# LED_Driver_and_LEDs_01.net
KiCad netlist of a schematic drawn in Altium Designer
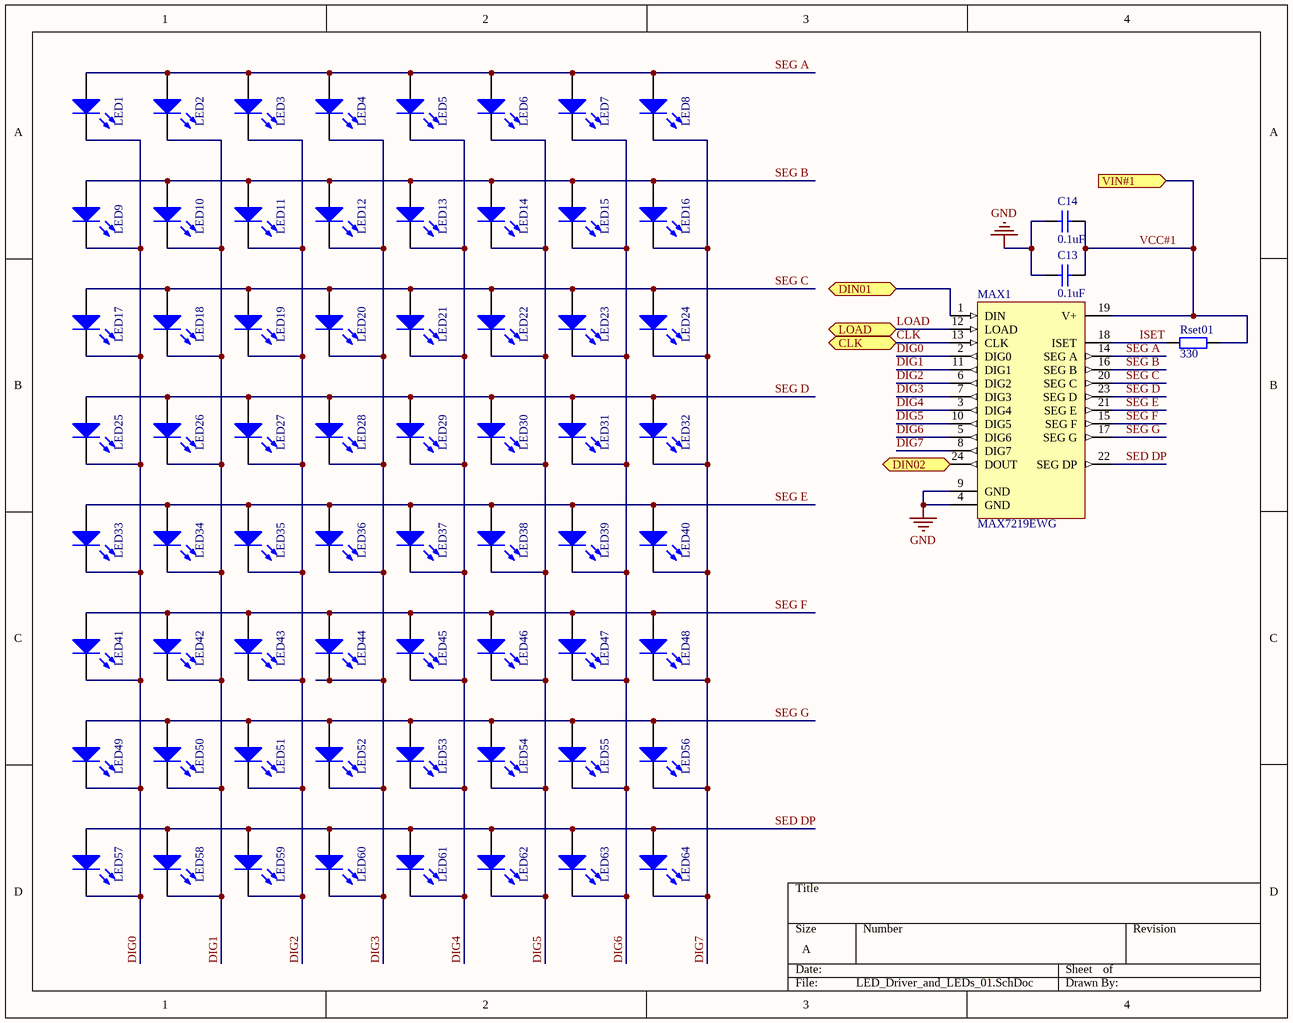
[diagram p0: LED_Driver_and_LEDs_01.SchDoc]

(export (version "E")
  (design (tool "Eeschema 10.0.6"))
  (components
    (comp (ref "C13")
      (value "0.1uF")
      (footprint "6-0805_N")
      (description "Capacitor (Semiconductor SIM Model)")
      (fields (field (name "Comment") "Cap Semi") (field (name "PUBLISHER") "Altium Limited"))
      (libsource (lib "Miscellaneous Devices") (part "Cap Semi"))
    )
    (comp (ref "C14")
      (value "0.1uF")
      (footprint "6-0805_N")
      (description "Capacitor (Semiconductor SIM Model)")
      (fields (field (name "Comment") "Cap Semi") (field (name "PUBLISHER") "Altium Limited"))
      (libsource (lib "Miscellaneous Devices") (part "Cap Semi"))
    )
    (comp (ref "LED1")
      (value "LED3")
      (footprint "3.5X2.8X1.9")
      (description "Typical BLUE SiC LED")
      (fields (field (name "PUBLISHER") "Altium Limited"))
      (libsource (lib "Miscellaneous Devices") (part "LED3"))
    )
    (comp (ref "LED2")
      (value "LED3")
      (footprint "3.5X2.8X1.9")
      (description "Typical BLUE SiC LED")
      (fields (field (name "PUBLISHER") "Altium Limited"))
      (libsource (lib "Miscellaneous Devices") (part "LED3"))
    )
    (comp (ref "LED3")
      (value "LED3")
      (footprint "3.5X2.8X1.9")
      (description "Typical BLUE SiC LED")
      (fields (field (name "PUBLISHER") "Altium Limited"))
      (libsource (lib "Miscellaneous Devices") (part "LED3"))
    )
    (comp (ref "LED4")
      (value "LED3")
      (footprint "3.5X2.8X1.9")
      (description "Typical BLUE SiC LED")
      (fields (field (name "PUBLISHER") "Altium Limited"))
      (libsource (lib "Miscellaneous Devices") (part "LED3"))
    )
    (comp (ref "LED5")
      (value "LED3")
      (footprint "3.5X2.8X1.9")
      (description "Typical BLUE SiC LED")
      (fields (field (name "PUBLISHER") "Altium Limited"))
      (libsource (lib "Miscellaneous Devices") (part "LED3"))
    )
    (comp (ref "LED6")
      (value "LED3")
      (footprint "3.5X2.8X1.9")
      (description "Typical BLUE SiC LED")
      (fields (field (name "PUBLISHER") "Altium Limited"))
      (libsource (lib "Miscellaneous Devices") (part "LED3"))
    )
    (comp (ref "LED7")
      (value "LED3")
      (footprint "3.5X2.8X1.9")
      (description "Typical BLUE SiC LED")
      (fields (field (name "PUBLISHER") "Altium Limited"))
      (libsource (lib "Miscellaneous Devices") (part "LED3"))
    )
    (comp (ref "LED8")
      (value "LED3")
      (footprint "3.5X2.8X1.9")
      (description "Typical BLUE SiC LED")
      (fields (field (name "PUBLISHER") "Altium Limited"))
      (libsource (lib "Miscellaneous Devices") (part "LED3"))
    )
    (comp (ref "LED9")
      (value "LED3")
      (footprint "3.5X2.8X1.9")
      (description "Typical BLUE SiC LED")
      (fields (field (name "PUBLISHER") "Altium Limited"))
      (libsource (lib "Miscellaneous Devices") (part "LED3"))
    )
    (comp (ref "LED10")
      (value "LED3")
      (footprint "3.5X2.8X1.9")
      (description "Typical BLUE SiC LED")
      (fields (field (name "PUBLISHER") "Altium Limited"))
      (libsource (lib "Miscellaneous Devices") (part "LED3"))
    )
    (comp (ref "LED11")
      (value "LED3")
      (footprint "3.5X2.8X1.9")
      (description "Typical BLUE SiC LED")
      (fields (field (name "PUBLISHER") "Altium Limited"))
      (libsource (lib "Miscellaneous Devices") (part "LED3"))
    )
    (comp (ref "LED12")
      (value "LED3")
      (footprint "3.5X2.8X1.9")
      (description "Typical BLUE SiC LED")
      (fields (field (name "PUBLISHER") "Altium Limited"))
      (libsource (lib "Miscellaneous Devices") (part "LED3"))
    )
    (comp (ref "LED13")
      (value "LED3")
      (footprint "3.5X2.8X1.9")
      (description "Typical BLUE SiC LED")
      (fields (field (name "PUBLISHER") "Altium Limited"))
      (libsource (lib "Miscellaneous Devices") (part "LED3"))
    )
    (comp (ref "LED14")
      (value "LED3")
      (footprint "3.5X2.8X1.9")
      (description "Typical BLUE SiC LED")
      (fields (field (name "PUBLISHER") "Altium Limited"))
      (libsource (lib "Miscellaneous Devices") (part "LED3"))
    )
    (comp (ref "LED15")
      (value "LED3")
      (footprint "3.5X2.8X1.9")
      (description "Typical BLUE SiC LED")
      (fields (field (name "PUBLISHER") "Altium Limited"))
      (libsource (lib "Miscellaneous Devices") (part "LED3"))
    )
    (comp (ref "LED16")
      (value "LED3")
      (footprint "3.5X2.8X1.9")
      (description "Typical BLUE SiC LED")
      (fields (field (name "PUBLISHER") "Altium Limited"))
      (libsource (lib "Miscellaneous Devices") (part "LED3"))
    )
    (comp (ref "LED17")
      (value "LED3")
      (footprint "3.5X2.8X1.9")
      (description "Typical BLUE SiC LED")
      (fields (field (name "PUBLISHER") "Altium Limited"))
      (libsource (lib "Miscellaneous Devices") (part "LED3"))
    )
    (comp (ref "LED18")
      (value "LED3")
      (footprint "3.5X2.8X1.9")
      (description "Typical BLUE SiC LED")
      (fields (field (name "PUBLISHER") "Altium Limited"))
      (libsource (lib "Miscellaneous Devices") (part "LED3"))
    )
    (comp (ref "LED19")
      (value "LED3")
      (footprint "3.5X2.8X1.9")
      (description "Typical BLUE SiC LED")
      (fields (field (name "PUBLISHER") "Altium Limited"))
      (libsource (lib "Miscellaneous Devices") (part "LED3"))
    )
    (comp (ref "LED20")
      (value "LED3")
      (footprint "3.5X2.8X1.9")
      (description "Typical BLUE SiC LED")
      (fields (field (name "PUBLISHER") "Altium Limited"))
      (libsource (lib "Miscellaneous Devices") (part "LED3"))
    )
    (comp (ref "LED21")
      (value "LED3")
      (footprint "3.5X2.8X1.9")
      (description "Typical BLUE SiC LED")
      (fields (field (name "PUBLISHER") "Altium Limited"))
      (libsource (lib "Miscellaneous Devices") (part "LED3"))
    )
    (comp (ref "LED22")
      (value "LED3")
      (footprint "3.5X2.8X1.9")
      (description "Typical BLUE SiC LED")
      (fields (field (name "PUBLISHER") "Altium Limited"))
      (libsource (lib "Miscellaneous Devices") (part "LED3"))
    )
    (comp (ref "LED23")
      (value "LED3")
      (footprint "3.5X2.8X1.9")
      (description "Typical BLUE SiC LED")
      (fields (field (name "PUBLISHER") "Altium Limited"))
      (libsource (lib "Miscellaneous Devices") (part "LED3"))
    )
    (comp (ref "LED24")
      (value "LED3")
      (footprint "3.5X2.8X1.9")
      (description "Typical BLUE SiC LED")
      (fields (field (name "PUBLISHER") "Altium Limited"))
      (libsource (lib "Miscellaneous Devices") (part "LED3"))
    )
    (comp (ref "LED25")
      (value "LED3")
      (footprint "3.5X2.8X1.9")
      (description "Typical BLUE SiC LED")
      (fields (field (name "PUBLISHER") "Altium Limited"))
      (libsource (lib "Miscellaneous Devices") (part "LED3"))
    )
    (comp (ref "LED26")
      (value "LED3")
      (footprint "3.5X2.8X1.9")
      (description "Typical BLUE SiC LED")
      (fields (field (name "PUBLISHER") "Altium Limited"))
      (libsource (lib "Miscellaneous Devices") (part "LED3"))
    )
    (comp (ref "LED27")
      (value "LED3")
      (footprint "3.5X2.8X1.9")
      (description "Typical BLUE SiC LED")
      (fields (field (name "PUBLISHER") "Altium Limited"))
      (libsource (lib "Miscellaneous Devices") (part "LED3"))
    )
    (comp (ref "LED28")
      (value "LED3")
      (footprint "3.5X2.8X1.9")
      (description "Typical BLUE SiC LED")
      (fields (field (name "PUBLISHER") "Altium Limited"))
      (libsource (lib "Miscellaneous Devices") (part "LED3"))
    )
    (comp (ref "LED29")
      (value "LED3")
      (footprint "3.5X2.8X1.9")
      (description "Typical BLUE SiC LED")
      (fields (field (name "PUBLISHER") "Altium Limited"))
      (libsource (lib "Miscellaneous Devices") (part "LED3"))
    )
    (comp (ref "LED30")
      (value "LED3")
      (footprint "3.5X2.8X1.9")
      (description "Typical BLUE SiC LED")
      (fields (field (name "PUBLISHER") "Altium Limited"))
      (libsource (lib "Miscellaneous Devices") (part "LED3"))
    )
    (comp (ref "LED31")
      (value "LED3")
      (footprint "3.5X2.8X1.9")
      (description "Typical BLUE SiC LED")
      (fields (field (name "PUBLISHER") "Altium Limited"))
      (libsource (lib "Miscellaneous Devices") (part "LED3"))
    )
    (comp (ref "LED32")
      (value "LED3")
      (footprint "3.5X2.8X1.9")
      (description "Typical BLUE SiC LED")
      (fields (field (name "PUBLISHER") "Altium Limited"))
      (libsource (lib "Miscellaneous Devices") (part "LED3"))
    )
    (comp (ref "LED33")
      (value "LED3")
      (footprint "3.5X2.8X1.9")
      (description "Typical BLUE SiC LED")
      (fields (field (name "PUBLISHER") "Altium Limited"))
      (libsource (lib "Miscellaneous Devices") (part "LED3"))
    )
    (comp (ref "LED34")
      (value "LED3")
      (footprint "3.5X2.8X1.9")
      (description "Typical BLUE SiC LED")
      (fields (field (name "PUBLISHER") "Altium Limited"))
      (libsource (lib "Miscellaneous Devices") (part "LED3"))
    )
    (comp (ref "LED35")
      (value "LED3")
      (footprint "3.5X2.8X1.9")
      (description "Typical BLUE SiC LED")
      (fields (field (name "PUBLISHER") "Altium Limited"))
      (libsource (lib "Miscellaneous Devices") (part "LED3"))
    )
    (comp (ref "LED36")
      (value "LED3")
      (footprint "3.5X2.8X1.9")
      (description "Typical BLUE SiC LED")
      (fields (field (name "PUBLISHER") "Altium Limited"))
      (libsource (lib "Miscellaneous Devices") (part "LED3"))
    )
    (comp (ref "LED37")
      (value "LED3")
      (footprint "3.5X2.8X1.9")
      (description "Typical BLUE SiC LED")
      (fields (field (name "PUBLISHER") "Altium Limited"))
      (libsource (lib "Miscellaneous Devices") (part "LED3"))
    )
    (comp (ref "LED38")
      (value "LED3")
      (footprint "3.5X2.8X1.9")
      (description "Typical BLUE SiC LED")
      (fields (field (name "PUBLISHER") "Altium Limited"))
      (libsource (lib "Miscellaneous Devices") (part "LED3"))
    )
    (comp (ref "LED39")
      (value "LED3")
      (footprint "3.5X2.8X1.9")
      (description "Typical BLUE SiC LED")
      (fields (field (name "PUBLISHER") "Altium Limited"))
      (libsource (lib "Miscellaneous Devices") (part "LED3"))
    )
    (comp (ref "LED40")
      (value "LED3")
      (footprint "3.5X2.8X1.9")
      (description "Typical BLUE SiC LED")
      (fields (field (name "PUBLISHER") "Altium Limited"))
      (libsource (lib "Miscellaneous Devices") (part "LED3"))
    )
    (comp (ref "LED41")
      (value "LED3")
      (footprint "3.5X2.8X1.9")
      (description "Typical BLUE SiC LED")
      (fields (field (name "PUBLISHER") "Altium Limited"))
      (libsource (lib "Miscellaneous Devices") (part "LED3"))
    )
    (comp (ref "LED42")
      (value "LED3")
      (footprint "3.5X2.8X1.9")
      (description "Typical BLUE SiC LED")
      (fields (field (name "PUBLISHER") "Altium Limited"))
      (libsource (lib "Miscellaneous Devices") (part "LED3"))
    )
    (comp (ref "LED43")
      (value "LED3")
      (footprint "3.5X2.8X1.9")
      (description "Typical BLUE SiC LED")
      (fields (field (name "PUBLISHER") "Altium Limited"))
      (libsource (lib "Miscellaneous Devices") (part "LED3"))
    )
    (comp (ref "LED44")
      (value "LED3")
      (footprint "3.5X2.8X1.9")
      (description "Typical BLUE SiC LED")
      (fields (field (name "PUBLISHER") "Altium Limited"))
      (libsource (lib "Miscellaneous Devices") (part "LED3"))
    )
    (comp (ref "LED45")
      (value "LED3")
      (footprint "3.5X2.8X1.9")
      (description "Typical BLUE SiC LED")
      (fields (field (name "PUBLISHER") "Altium Limited"))
      (libsource (lib "Miscellaneous Devices") (part "LED3"))
    )
    (comp (ref "LED46")
      (value "LED3")
      (footprint "3.5X2.8X1.9")
      (description "Typical BLUE SiC LED")
      (fields (field (name "PUBLISHER") "Altium Limited"))
      (libsource (lib "Miscellaneous Devices") (part "LED3"))
    )
    (comp (ref "LED47")
      (value "LED3")
      (footprint "3.5X2.8X1.9")
      (description "Typical BLUE SiC LED")
      (fields (field (name "PUBLISHER") "Altium Limited"))
      (libsource (lib "Miscellaneous Devices") (part "LED3"))
    )
    (comp (ref "LED48")
      (value "LED3")
      (footprint "3.5X2.8X1.9")
      (description "Typical BLUE SiC LED")
      (fields (field (name "PUBLISHER") "Altium Limited"))
      (libsource (lib "Miscellaneous Devices") (part "LED3"))
    )
    (comp (ref "LED49")
      (value "LED3")
      (footprint "3.5X2.8X1.9")
      (description "Typical BLUE SiC LED")
      (fields (field (name "PUBLISHER") "Altium Limited"))
      (libsource (lib "Miscellaneous Devices") (part "LED3"))
    )
    (comp (ref "LED50")
      (value "LED3")
      (footprint "3.5X2.8X1.9")
      (description "Typical BLUE SiC LED")
      (fields (field (name "PUBLISHER") "Altium Limited"))
      (libsource (lib "Miscellaneous Devices") (part "LED3"))
    )
    (comp (ref "LED51")
      (value "LED3")
      (footprint "3.5X2.8X1.9")
      (description "Typical BLUE SiC LED")
      (fields (field (name "PUBLISHER") "Altium Limited"))
      (libsource (lib "Miscellaneous Devices") (part "LED3"))
    )
    (comp (ref "LED52")
      (value "LED3")
      (footprint "3.5X2.8X1.9")
      (description "Typical BLUE SiC LED")
      (fields (field (name "PUBLISHER") "Altium Limited"))
      (libsource (lib "Miscellaneous Devices") (part "LED3"))
    )
    (comp (ref "LED53")
      (value "LED3")
      (footprint "3.5X2.8X1.9")
      (description "Typical BLUE SiC LED")
      (fields (field (name "PUBLISHER") "Altium Limited"))
      (libsource (lib "Miscellaneous Devices") (part "LED3"))
    )
    (comp (ref "LED54")
      (value "LED3")
      (footprint "3.5X2.8X1.9")
      (description "Typical BLUE SiC LED")
      (fields (field (name "PUBLISHER") "Altium Limited"))
      (libsource (lib "Miscellaneous Devices") (part "LED3"))
    )
    (comp (ref "LED55")
      (value "LED3")
      (footprint "3.5X2.8X1.9")
      (description "Typical BLUE SiC LED")
      (fields (field (name "PUBLISHER") "Altium Limited"))
      (libsource (lib "Miscellaneous Devices") (part "LED3"))
    )
    (comp (ref "LED56")
      (value "LED3")
      (footprint "3.5X2.8X1.9")
      (description "Typical BLUE SiC LED")
      (fields (field (name "PUBLISHER") "Altium Limited"))
      (libsource (lib "Miscellaneous Devices") (part "LED3"))
    )
    (comp (ref "LED57")
      (value "LED3")
      (footprint "3.5X2.8X1.9")
      (description "Typical BLUE SiC LED")
      (fields (field (name "PUBLISHER") "Altium Limited"))
      (libsource (lib "Miscellaneous Devices") (part "LED3"))
    )
    (comp (ref "LED58")
      (value "LED3")
      (footprint "3.5X2.8X1.9")
      (description "Typical BLUE SiC LED")
      (fields (field (name "PUBLISHER") "Altium Limited"))
      (libsource (lib "Miscellaneous Devices") (part "LED3"))
    )
    (comp (ref "LED59")
      (value "LED3")
      (footprint "3.5X2.8X1.9")
      (description "Typical BLUE SiC LED")
      (fields (field (name "PUBLISHER") "Altium Limited"))
      (libsource (lib "Miscellaneous Devices") (part "LED3"))
    )
    (comp (ref "LED60")
      (value "LED3")
      (footprint "3.5X2.8X1.9")
      (description "Typical BLUE SiC LED")
      (fields (field (name "PUBLISHER") "Altium Limited"))
      (libsource (lib "Miscellaneous Devices") (part "LED3"))
    )
    (comp (ref "LED61")
      (value "LED3")
      (footprint "3.5X2.8X1.9")
      (description "Typical BLUE SiC LED")
      (fields (field (name "PUBLISHER") "Altium Limited"))
      (libsource (lib "Miscellaneous Devices") (part "LED3"))
    )
    (comp (ref "LED62")
      (value "LED3")
      (footprint "3.5X2.8X1.9")
      (description "Typical BLUE SiC LED")
      (fields (field (name "PUBLISHER") "Altium Limited"))
      (libsource (lib "Miscellaneous Devices") (part "LED3"))
    )
    (comp (ref "LED63")
      (value "LED3")
      (footprint "3.5X2.8X1.9")
      (description "Typical BLUE SiC LED")
      (fields (field (name "PUBLISHER") "Altium Limited"))
      (libsource (lib "Miscellaneous Devices") (part "LED3"))
    )
    (comp (ref "LED64")
      (value "LED3")
      (footprint "3.5X2.8X1.9")
      (description "Typical BLUE SiC LED")
      (fields (field (name "PUBLISHER") "Altium Limited"))
      (libsource (lib "Miscellaneous Devices") (part "LED3"))
    )
    (comp (ref "MAX1")
      (value "MAX7219EWG")
      (footprint "WSO24_N")
      (description "Serially Interfaced, 8-Digit LED Display Driver")
      (fields (field (name "PUBLISHER") "Altium Limited"))
      (libsource (lib "Maxim Interface Display Driver") (part "MAX7219EWG"))
    )
    (comp (ref "Rset01")
      (value "330")
      (footprint "J1-0603")
      (description "Resistor")
      (fields (field (name "Comment") "Res2") (field (name "PUBLISHER") "Altium Limited"))
      (libsource (lib "Miscellaneous Devices") (part "Res2"))
    )
  )
  (nets
    (net (code "1") (name "/CLK") (class "Default")
      (node (ref "MAX1") (pin "13") (pinfunction "CLK_13") (pintype "input"))
    )
    (net (code "2") (name "/DIG0") (class "Default")
      (node (ref "LED1") (pin "2") (pinfunction "K_2") (pintype "passive"))
      (node (ref "LED17") (pin "2") (pinfunction "K_2") (pintype "passive"))
      (node (ref "LED25") (pin "2") (pinfunction "K_2") (pintype "passive"))
      (node (ref "LED33") (pin "2") (pinfunction "K_2") (pintype "passive"))
      (node (ref "LED41") (pin "2") (pinfunction "K_2") (pintype "passive"))
      (node (ref "LED49") (pin "2") (pinfunction "K_2") (pintype "passive"))
      (node (ref "LED57") (pin "2") (pinfunction "K_2") (pintype "passive"))
      (node (ref "LED9") (pin "2") (pinfunction "K_2") (pintype "passive"))
      (node (ref "MAX1") (pin "2") (pinfunction "DIG0_2") (pintype "output"))
    )
    (net (code "3") (name "/DIG1") (class "Default")
      (node (ref "LED10") (pin "2") (pinfunction "K_2") (pintype "passive"))
      (node (ref "LED18") (pin "2") (pinfunction "K_2") (pintype "passive"))
      (node (ref "LED2") (pin "2") (pinfunction "K_2") (pintype "passive"))
      (node (ref "LED26") (pin "2") (pinfunction "K_2") (pintype "passive"))
      (node (ref "LED34") (pin "2") (pinfunction "K_2") (pintype "passive"))
      (node (ref "LED42") (pin "2") (pinfunction "K_2") (pintype "passive"))
      (node (ref "LED50") (pin "2") (pinfunction "K_2") (pintype "passive"))
      (node (ref "LED58") (pin "2") (pinfunction "K_2") (pintype "passive"))
      (node (ref "MAX1") (pin "11") (pinfunction "DIG1_11") (pintype "output"))
    )
    (net (code "4") (name "/DIG2") (class "Default")
      (node (ref "LED11") (pin "2") (pinfunction "K_2") (pintype "passive"))
      (node (ref "LED19") (pin "2") (pinfunction "K_2") (pintype "passive"))
      (node (ref "LED27") (pin "2") (pinfunction "K_2") (pintype "passive"))
      (node (ref "LED3") (pin "2") (pinfunction "K_2") (pintype "passive"))
      (node (ref "LED35") (pin "2") (pinfunction "K_2") (pintype "passive"))
      (node (ref "LED43") (pin "2") (pinfunction "K_2") (pintype "passive"))
      (node (ref "LED51") (pin "2") (pinfunction "K_2") (pintype "passive"))
      (node (ref "LED59") (pin "2") (pinfunction "K_2") (pintype "passive"))
      (node (ref "MAX1") (pin "6") (pinfunction "DIG2_6") (pintype "output"))
    )
    (net (code "5") (name "/DIG3") (class "Default")
      (node (ref "LED12") (pin "2") (pinfunction "K_2") (pintype "passive"))
      (node (ref "LED20") (pin "2") (pinfunction "K_2") (pintype "passive"))
      (node (ref "LED28") (pin "2") (pinfunction "K_2") (pintype "passive"))
      (node (ref "LED36") (pin "2") (pinfunction "K_2") (pintype "passive"))
      (node (ref "LED4") (pin "2") (pinfunction "K_2") (pintype "passive"))
      (node (ref "LED44") (pin "2") (pinfunction "K_2") (pintype "passive"))
      (node (ref "LED52") (pin "2") (pinfunction "K_2") (pintype "passive"))
      (node (ref "LED60") (pin "2") (pinfunction "K_2") (pintype "passive"))
      (node (ref "MAX1") (pin "7") (pinfunction "DIG3_7") (pintype "output"))
    )
    (net (code "6") (name "/DIG4") (class "Default")
      (node (ref "LED13") (pin "2") (pinfunction "K_2") (pintype "passive"))
      (node (ref "LED21") (pin "2") (pinfunction "K_2") (pintype "passive"))
      (node (ref "LED29") (pin "2") (pinfunction "K_2") (pintype "passive"))
      (node (ref "LED37") (pin "2") (pinfunction "K_2") (pintype "passive"))
      (node (ref "LED45") (pin "2") (pinfunction "K_2") (pintype "passive"))
      (node (ref "LED5") (pin "2") (pinfunction "K_2") (pintype "passive"))
      (node (ref "LED53") (pin "2") (pinfunction "K_2") (pintype "passive"))
      (node (ref "LED61") (pin "2") (pinfunction "K_2") (pintype "passive"))
      (node (ref "MAX1") (pin "3") (pinfunction "DIG4_3") (pintype "output"))
    )
    (net (code "7") (name "/DIG5") (class "Default")
      (node (ref "LED14") (pin "2") (pinfunction "K_2") (pintype "passive"))
      (node (ref "LED22") (pin "2") (pinfunction "K_2") (pintype "passive"))
      (node (ref "LED30") (pin "2") (pinfunction "K_2") (pintype "passive"))
      (node (ref "LED38") (pin "2") (pinfunction "K_2") (pintype "passive"))
      (node (ref "LED46") (pin "2") (pinfunction "K_2") (pintype "passive"))
      (node (ref "LED54") (pin "2") (pinfunction "K_2") (pintype "passive"))
      (node (ref "LED6") (pin "2") (pinfunction "K_2") (pintype "passive"))
      (node (ref "LED62") (pin "2") (pinfunction "K_2") (pintype "passive"))
      (node (ref "MAX1") (pin "10") (pinfunction "DIG5_10") (pintype "output"))
    )
    (net (code "8") (name "/DIG6") (class "Default")
      (node (ref "LED15") (pin "2") (pinfunction "K_2") (pintype "passive"))
      (node (ref "LED23") (pin "2") (pinfunction "K_2") (pintype "passive"))
      (node (ref "LED31") (pin "2") (pinfunction "K_2") (pintype "passive"))
      (node (ref "LED39") (pin "2") (pinfunction "K_2") (pintype "passive"))
      (node (ref "LED47") (pin "2") (pinfunction "K_2") (pintype "passive"))
      (node (ref "LED55") (pin "2") (pinfunction "K_2") (pintype "passive"))
      (node (ref "LED63") (pin "2") (pinfunction "K_2") (pintype "passive"))
      (node (ref "LED7") (pin "2") (pinfunction "K_2") (pintype "passive"))
      (node (ref "MAX1") (pin "5") (pinfunction "DIG6_5") (pintype "output"))
    )
    (net (code "9") (name "/DIG7") (class "Default")
      (node (ref "LED16") (pin "2") (pinfunction "K_2") (pintype "passive"))
      (node (ref "LED24") (pin "2") (pinfunction "K_2") (pintype "passive"))
      (node (ref "LED32") (pin "2") (pinfunction "K_2") (pintype "passive"))
      (node (ref "LED40") (pin "2") (pinfunction "K_2") (pintype "passive"))
      (node (ref "LED48") (pin "2") (pinfunction "K_2") (pintype "passive"))
      (node (ref "LED56") (pin "2") (pinfunction "K_2") (pintype "passive"))
      (node (ref "LED64") (pin "2") (pinfunction "K_2") (pintype "passive"))
      (node (ref "LED8") (pin "2") (pinfunction "K_2") (pintype "passive"))
      (node (ref "MAX1") (pin "8") (pinfunction "DIG7_8") (pintype "output"))
    )
    (net (code "10") (name "/DIN01") (class "Default")
      (node (ref "MAX1") (pin "1") (pinfunction "DIN_1") (pintype "input"))
    )
    (net (code "11") (name "/DIN02") (class "Default")
      (node (ref "MAX1") (pin "24") (pinfunction "DOUT_24") (pintype "output"))
    )
    (net (code "12") (name "/ISET") (class "Default")
      (node (ref "MAX1") (pin "18") (pinfunction "ISET_18") (pintype "passive"))
      (node (ref "Rset01") (pin "2") (pinfunction "2_2") (pintype "passive"))
    )
    (net (code "13") (name "/LOAD") (class "Default")
      (node (ref "MAX1") (pin "12") (pinfunction "LOAD_12") (pintype "input"))
    )
    (net (code "14") (name "/SED DP") (class "Default")
      (node (ref "LED57") (pin "1") (pinfunction "A_1") (pintype "passive"))
      (node (ref "LED58") (pin "1") (pinfunction "A_1") (pintype "passive"))
      (node (ref "LED59") (pin "1") (pinfunction "A_1") (pintype "passive"))
      (node (ref "LED60") (pin "1") (pinfunction "A_1") (pintype "passive"))
      (node (ref "LED61") (pin "1") (pinfunction "A_1") (pintype "passive"))
      (node (ref "LED62") (pin "1") (pinfunction "A_1") (pintype "passive"))
      (node (ref "LED63") (pin "1") (pinfunction "A_1") (pintype "passive"))
      (node (ref "LED64") (pin "1") (pinfunction "A_1") (pintype "passive"))
      (node (ref "MAX1") (pin "22") (pinfunction "SEG_DP_22") (pintype "output"))
    )
    (net (code "15") (name "/SEG A") (class "Default")
      (node (ref "LED1") (pin "1") (pinfunction "A_1") (pintype "passive"))
      (node (ref "LED2") (pin "1") (pinfunction "A_1") (pintype "passive"))
      (node (ref "LED3") (pin "1") (pinfunction "A_1") (pintype "passive"))
      (node (ref "LED4") (pin "1") (pinfunction "A_1") (pintype "passive"))
      (node (ref "LED5") (pin "1") (pinfunction "A_1") (pintype "passive"))
      (node (ref "LED6") (pin "1") (pinfunction "A_1") (pintype "passive"))
      (node (ref "LED7") (pin "1") (pinfunction "A_1") (pintype "passive"))
      (node (ref "LED8") (pin "1") (pinfunction "A_1") (pintype "passive"))
      (node (ref "MAX1") (pin "14") (pinfunction "SEG_A_14") (pintype "output"))
    )
    (net (code "16") (name "/SEG B") (class "Default")
      (node (ref "LED10") (pin "1") (pinfunction "A_1") (pintype "passive"))
      (node (ref "LED11") (pin "1") (pinfunction "A_1") (pintype "passive"))
      (node (ref "LED12") (pin "1") (pinfunction "A_1") (pintype "passive"))
      (node (ref "LED13") (pin "1") (pinfunction "A_1") (pintype "passive"))
      (node (ref "LED14") (pin "1") (pinfunction "A_1") (pintype "passive"))
      (node (ref "LED15") (pin "1") (pinfunction "A_1") (pintype "passive"))
      (node (ref "LED16") (pin "1") (pinfunction "A_1") (pintype "passive"))
      (node (ref "LED9") (pin "1") (pinfunction "A_1") (pintype "passive"))
      (node (ref "MAX1") (pin "16") (pinfunction "SEG_B_16") (pintype "output"))
    )
    (net (code "17") (name "/SEG C") (class "Default")
      (node (ref "LED17") (pin "1") (pinfunction "A_1") (pintype "passive"))
      (node (ref "LED18") (pin "1") (pinfunction "A_1") (pintype "passive"))
      (node (ref "LED19") (pin "1") (pinfunction "A_1") (pintype "passive"))
      (node (ref "LED20") (pin "1") (pinfunction "A_1") (pintype "passive"))
      (node (ref "LED21") (pin "1") (pinfunction "A_1") (pintype "passive"))
      (node (ref "LED22") (pin "1") (pinfunction "A_1") (pintype "passive"))
      (node (ref "LED23") (pin "1") (pinfunction "A_1") (pintype "passive"))
      (node (ref "LED24") (pin "1") (pinfunction "A_1") (pintype "passive"))
      (node (ref "MAX1") (pin "20") (pinfunction "SEG_C_20") (pintype "output"))
    )
    (net (code "18") (name "/SEG D") (class "Default")
      (node (ref "LED25") (pin "1") (pinfunction "A_1") (pintype "passive"))
      (node (ref "LED26") (pin "1") (pinfunction "A_1") (pintype "passive"))
      (node (ref "LED27") (pin "1") (pinfunction "A_1") (pintype "passive"))
      (node (ref "LED28") (pin "1") (pinfunction "A_1") (pintype "passive"))
      (node (ref "LED29") (pin "1") (pinfunction "A_1") (pintype "passive"))
      (node (ref "LED30") (pin "1") (pinfunction "A_1") (pintype "passive"))
      (node (ref "LED31") (pin "1") (pinfunction "A_1") (pintype "passive"))
      (node (ref "LED32") (pin "1") (pinfunction "A_1") (pintype "passive"))
      (node (ref "MAX1") (pin "23") (pinfunction "SEG_D_23") (pintype "output"))
    )
    (net (code "19") (name "/SEG E") (class "Default")
      (node (ref "LED33") (pin "1") (pinfunction "A_1") (pintype "passive"))
      (node (ref "LED34") (pin "1") (pinfunction "A_1") (pintype "passive"))
      (node (ref "LED35") (pin "1") (pinfunction "A_1") (pintype "passive"))
      (node (ref "LED36") (pin "1") (pinfunction "A_1") (pintype "passive"))
      (node (ref "LED37") (pin "1") (pinfunction "A_1") (pintype "passive"))
      (node (ref "LED38") (pin "1") (pinfunction "A_1") (pintype "passive"))
      (node (ref "LED39") (pin "1") (pinfunction "A_1") (pintype "passive"))
      (node (ref "LED40") (pin "1") (pinfunction "A_1") (pintype "passive"))
      (node (ref "MAX1") (pin "21") (pinfunction "SEG_E_21") (pintype "output"))
    )
    (net (code "20") (name "/SEG F") (class "Default")
      (node (ref "LED41") (pin "1") (pinfunction "A_1") (pintype "passive"))
      (node (ref "LED42") (pin "1") (pinfunction "A_1") (pintype "passive"))
      (node (ref "LED43") (pin "1") (pinfunction "A_1") (pintype "passive"))
      (node (ref "LED44") (pin "1") (pinfunction "A_1") (pintype "passive"))
      (node (ref "LED45") (pin "1") (pinfunction "A_1") (pintype "passive"))
      (node (ref "LED46") (pin "1") (pinfunction "A_1") (pintype "passive"))
      (node (ref "LED47") (pin "1") (pinfunction "A_1") (pintype "passive"))
      (node (ref "LED48") (pin "1") (pinfunction "A_1") (pintype "passive"))
      (node (ref "MAX1") (pin "15") (pinfunction "SEG_F_15") (pintype "output"))
    )
    (net (code "21") (name "/SEG G") (class "Default")
      (node (ref "LED49") (pin "1") (pinfunction "A_1") (pintype "passive"))
      (node (ref "LED50") (pin "1") (pinfunction "A_1") (pintype "passive"))
      (node (ref "LED51") (pin "1") (pinfunction "A_1") (pintype "passive"))
      (node (ref "LED52") (pin "1") (pinfunction "A_1") (pintype "passive"))
      (node (ref "LED53") (pin "1") (pinfunction "A_1") (pintype "passive"))
      (node (ref "LED54") (pin "1") (pinfunction "A_1") (pintype "passive"))
      (node (ref "LED55") (pin "1") (pinfunction "A_1") (pintype "passive"))
      (node (ref "LED56") (pin "1") (pinfunction "A_1") (pintype "passive"))
      (node (ref "MAX1") (pin "17") (pinfunction "SEG_G_17") (pintype "output"))
    )
    (net (code "22") (name "/VCC#1") (class "Default")
      (node (ref "C13") (pin "1") (pinfunction "1_1") (pintype "passive"))
      (node (ref "C14") (pin "1") (pinfunction "1_1") (pintype "passive"))
      (node (ref "MAX1") (pin "19") (pinfunction "V+_19") (pintype "power_in"))
      (node (ref "Rset01") (pin "1") (pinfunction "1_1") (pintype "passive"))
    )
    (net (code "23") (name "GND") (class "Default")
      (node (ref "C13") (pin "2") (pinfunction "2_2") (pintype "passive"))
      (node (ref "C14") (pin "2") (pinfunction "2_2") (pintype "passive"))
      (node (ref "MAX1") (pin "4") (pinfunction "GND_4") (pintype "power_in"))
      (node (ref "MAX1") (pin "9") (pinfunction "GND_9") (pintype "power_in"))
    )
  )
)
